# charliewatch-norf.net
KiCad netlist of a schematic drawn in EAGLE
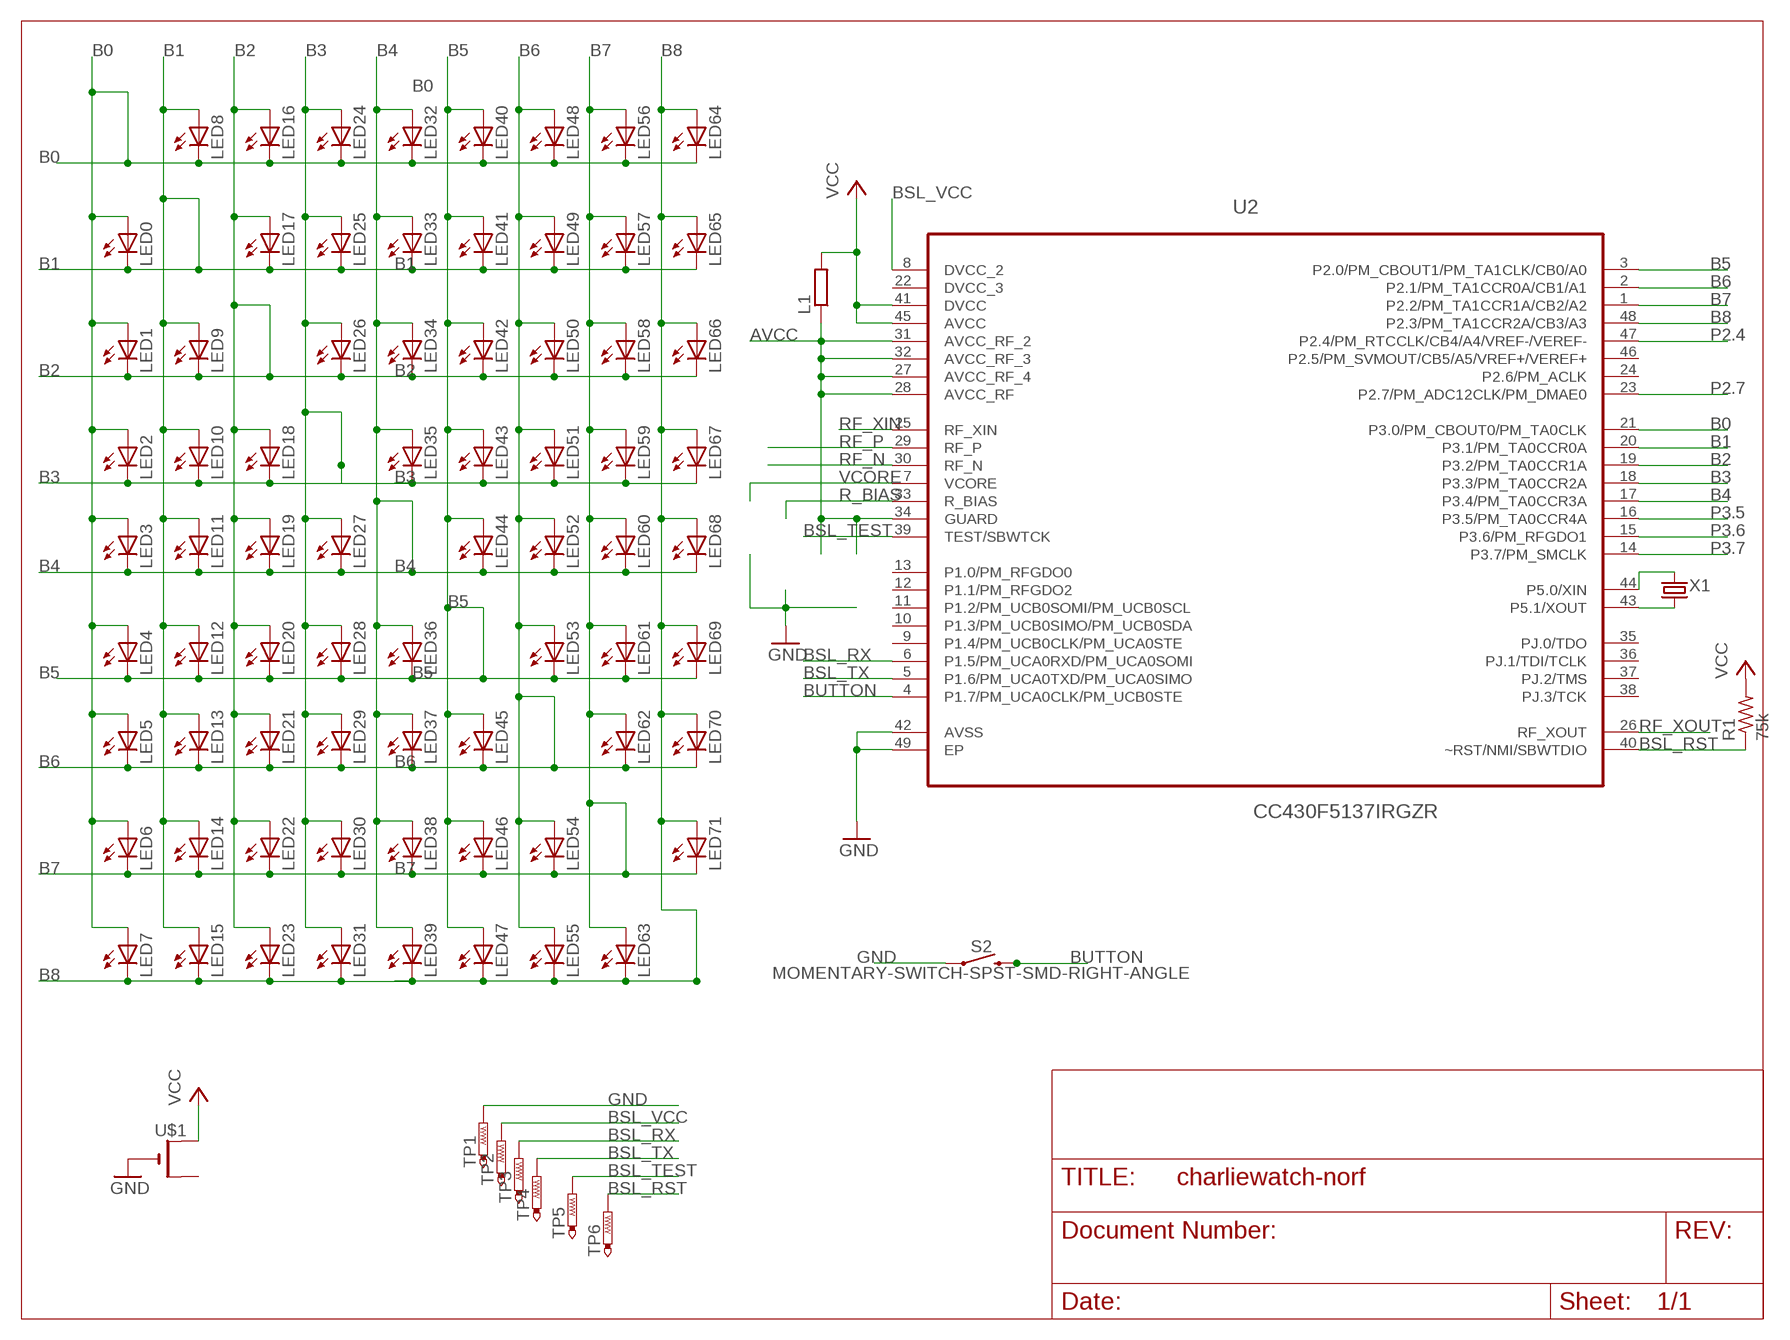
[diagram p0: schematic, sheet 1]

(export (version "E")
  (design (tool "Eeschema 10.0.6"))
  (components
    (comp (ref "L1")
      (value "R-EU_R0603")
      (footprint "eagle-import:R0603")
      (libsource (lib "eagle-import") (part "R-EU_R0603"))
    )
    (comp (ref "LED0")
      (value "LEDCHIPLED_0603")
      (footprint "eagle-import:CHIPLED_0603")
      (libsource (lib "eagle-import") (part "LEDCHIPLED_0603"))
    )
    (comp (ref "LED1")
      (value "LEDCHIPLED_0603")
      (footprint "eagle-import:CHIPLED_0603")
      (libsource (lib "eagle-import") (part "LEDCHIPLED_0603"))
    )
    (comp (ref "LED2")
      (value "LEDCHIPLED_0603")
      (footprint "eagle-import:CHIPLED_0603")
      (libsource (lib "eagle-import") (part "LEDCHIPLED_0603"))
    )
    (comp (ref "LED3")
      (value "LEDCHIPLED_0603")
      (footprint "eagle-import:CHIPLED_0603")
      (libsource (lib "eagle-import") (part "LEDCHIPLED_0603"))
    )
    (comp (ref "LED4")
      (value "LEDCHIPLED_0603")
      (footprint "eagle-import:CHIPLED_0603")
      (libsource (lib "eagle-import") (part "LEDCHIPLED_0603"))
    )
    (comp (ref "LED5")
      (value "LEDCHIPLED_0603")
      (footprint "eagle-import:CHIPLED_0603")
      (libsource (lib "eagle-import") (part "LEDCHIPLED_0603"))
    )
    (comp (ref "LED6")
      (value "LEDCHIPLED_0603")
      (footprint "eagle-import:CHIPLED_0603")
      (libsource (lib "eagle-import") (part "LEDCHIPLED_0603"))
    )
    (comp (ref "LED7")
      (value "LEDCHIPLED_0603")
      (footprint "eagle-import:CHIPLED_0603")
      (libsource (lib "eagle-import") (part "LEDCHIPLED_0603"))
    )
    (comp (ref "LED8")
      (value "LEDCHIPLED_0603")
      (footprint "eagle-import:CHIPLED_0603")
      (libsource (lib "eagle-import") (part "LEDCHIPLED_0603"))
    )
    (comp (ref "LED9")
      (value "LEDCHIPLED_0603")
      (footprint "eagle-import:CHIPLED_0603")
      (libsource (lib "eagle-import") (part "LEDCHIPLED_0603"))
    )
    (comp (ref "LED10")
      (value "LEDCHIPLED_0603")
      (footprint "eagle-import:CHIPLED_0603")
      (libsource (lib "eagle-import") (part "LEDCHIPLED_0603"))
    )
    (comp (ref "LED11")
      (value "LEDCHIPLED_0603")
      (footprint "eagle-import:CHIPLED_0603")
      (libsource (lib "eagle-import") (part "LEDCHIPLED_0603"))
    )
    (comp (ref "LED12")
      (value "LEDCHIPLED_0603")
      (footprint "eagle-import:CHIPLED_0603")
      (libsource (lib "eagle-import") (part "LEDCHIPLED_0603"))
    )
    (comp (ref "LED13")
      (value "LEDCHIPLED_0603")
      (footprint "eagle-import:CHIPLED_0603")
      (libsource (lib "eagle-import") (part "LEDCHIPLED_0603"))
    )
    (comp (ref "LED14")
      (value "LEDCHIPLED_0603")
      (footprint "eagle-import:CHIPLED_0603")
      (libsource (lib "eagle-import") (part "LEDCHIPLED_0603"))
    )
    (comp (ref "LED15")
      (value "LEDCHIPLED_0603")
      (footprint "eagle-import:CHIPLED_0603")
      (libsource (lib "eagle-import") (part "LEDCHIPLED_0603"))
    )
    (comp (ref "LED16")
      (value "LEDCHIPLED_0603")
      (footprint "eagle-import:CHIPLED_0603")
      (libsource (lib "eagle-import") (part "LEDCHIPLED_0603"))
    )
    (comp (ref "LED17")
      (value "LEDCHIPLED_0603")
      (footprint "eagle-import:CHIPLED_0603")
      (libsource (lib "eagle-import") (part "LEDCHIPLED_0603"))
    )
    (comp (ref "LED18")
      (value "LEDCHIPLED_0603")
      (footprint "eagle-import:CHIPLED_0603")
      (libsource (lib "eagle-import") (part "LEDCHIPLED_0603"))
    )
    (comp (ref "LED19")
      (value "LEDCHIPLED_0603")
      (footprint "eagle-import:CHIPLED_0603")
      (libsource (lib "eagle-import") (part "LEDCHIPLED_0603"))
    )
    (comp (ref "LED20")
      (value "LEDCHIPLED_0603")
      (footprint "eagle-import:CHIPLED_0603")
      (libsource (lib "eagle-import") (part "LEDCHIPLED_0603"))
    )
    (comp (ref "LED21")
      (value "LEDCHIPLED_0603")
      (footprint "eagle-import:CHIPLED_0603")
      (libsource (lib "eagle-import") (part "LEDCHIPLED_0603"))
    )
    (comp (ref "LED22")
      (value "LEDCHIPLED_0603")
      (footprint "eagle-import:CHIPLED_0603")
      (libsource (lib "eagle-import") (part "LEDCHIPLED_0603"))
    )
    (comp (ref "LED23")
      (value "LEDCHIPLED_0603")
      (footprint "eagle-import:CHIPLED_0603")
      (libsource (lib "eagle-import") (part "LEDCHIPLED_0603"))
    )
    (comp (ref "LED24")
      (value "LEDCHIPLED_0603")
      (footprint "eagle-import:CHIPLED_0603")
      (libsource (lib "eagle-import") (part "LEDCHIPLED_0603"))
    )
    (comp (ref "LED25")
      (value "LEDCHIPLED_0603")
      (footprint "eagle-import:CHIPLED_0603")
      (libsource (lib "eagle-import") (part "LEDCHIPLED_0603"))
    )
    (comp (ref "LED26")
      (value "LEDCHIPLED_0603")
      (footprint "eagle-import:CHIPLED_0603")
      (libsource (lib "eagle-import") (part "LEDCHIPLED_0603"))
    )
    (comp (ref "LED27")
      (value "LEDCHIPLED_0603")
      (footprint "eagle-import:CHIPLED_0603")
      (libsource (lib "eagle-import") (part "LEDCHIPLED_0603"))
    )
    (comp (ref "LED28")
      (value "LEDCHIPLED_0603")
      (footprint "eagle-import:CHIPLED_0603")
      (libsource (lib "eagle-import") (part "LEDCHIPLED_0603"))
    )
    (comp (ref "LED29")
      (value "LEDCHIPLED_0603")
      (footprint "eagle-import:CHIPLED_0603")
      (libsource (lib "eagle-import") (part "LEDCHIPLED_0603"))
    )
    (comp (ref "LED30")
      (value "LEDCHIPLED_0603")
      (footprint "eagle-import:CHIPLED_0603")
      (libsource (lib "eagle-import") (part "LEDCHIPLED_0603"))
    )
    (comp (ref "LED31")
      (value "LEDCHIPLED_0603")
      (footprint "eagle-import:CHIPLED_0603")
      (libsource (lib "eagle-import") (part "LEDCHIPLED_0603"))
    )
    (comp (ref "LED32")
      (value "LEDCHIPLED_0603")
      (footprint "eagle-import:CHIPLED_0603")
      (libsource (lib "eagle-import") (part "LEDCHIPLED_0603"))
    )
    (comp (ref "LED33")
      (value "LEDCHIPLED_0603")
      (footprint "eagle-import:CHIPLED_0603")
      (libsource (lib "eagle-import") (part "LEDCHIPLED_0603"))
    )
    (comp (ref "LED34")
      (value "LEDCHIPLED_0603")
      (footprint "eagle-import:CHIPLED_0603")
      (libsource (lib "eagle-import") (part "LEDCHIPLED_0603"))
    )
    (comp (ref "LED35")
      (value "LEDCHIPLED_0603")
      (footprint "eagle-import:CHIPLED_0603")
      (libsource (lib "eagle-import") (part "LEDCHIPLED_0603"))
    )
    (comp (ref "LED36")
      (value "LEDCHIPLED_0603")
      (footprint "eagle-import:CHIPLED_0603")
      (libsource (lib "eagle-import") (part "LEDCHIPLED_0603"))
    )
    (comp (ref "LED37")
      (value "LEDCHIPLED_0603")
      (footprint "eagle-import:CHIPLED_0603")
      (libsource (lib "eagle-import") (part "LEDCHIPLED_0603"))
    )
    (comp (ref "LED38")
      (value "LEDCHIPLED_0603")
      (footprint "eagle-import:CHIPLED_0603")
      (libsource (lib "eagle-import") (part "LEDCHIPLED_0603"))
    )
    (comp (ref "LED39")
      (value "LEDCHIPLED_0603")
      (footprint "eagle-import:CHIPLED_0603")
      (libsource (lib "eagle-import") (part "LEDCHIPLED_0603"))
    )
    (comp (ref "LED40")
      (value "LEDCHIPLED_0603")
      (footprint "eagle-import:CHIPLED_0603")
      (libsource (lib "eagle-import") (part "LEDCHIPLED_0603"))
    )
    (comp (ref "LED41")
      (value "LEDCHIPLED_0603")
      (footprint "eagle-import:CHIPLED_0603")
      (libsource (lib "eagle-import") (part "LEDCHIPLED_0603"))
    )
    (comp (ref "LED42")
      (value "LEDCHIPLED_0603")
      (footprint "eagle-import:CHIPLED_0603")
      (libsource (lib "eagle-import") (part "LEDCHIPLED_0603"))
    )
    (comp (ref "LED43")
      (value "LEDCHIPLED_0603")
      (footprint "eagle-import:CHIPLED_0603")
      (libsource (lib "eagle-import") (part "LEDCHIPLED_0603"))
    )
    (comp (ref "LED44")
      (value "LEDCHIPLED_0603")
      (footprint "eagle-import:CHIPLED_0603")
      (libsource (lib "eagle-import") (part "LEDCHIPLED_0603"))
    )
    (comp (ref "LED45")
      (value "LEDCHIPLED_0603")
      (footprint "eagle-import:CHIPLED_0603")
      (libsource (lib "eagle-import") (part "LEDCHIPLED_0603"))
    )
    (comp (ref "LED46")
      (value "LEDCHIPLED_0603")
      (footprint "eagle-import:CHIPLED_0603")
      (libsource (lib "eagle-import") (part "LEDCHIPLED_0603"))
    )
    (comp (ref "LED47")
      (value "LEDCHIPLED_0603")
      (footprint "eagle-import:CHIPLED_0603")
      (libsource (lib "eagle-import") (part "LEDCHIPLED_0603"))
    )
    (comp (ref "LED48")
      (value "LEDCHIPLED_0603")
      (footprint "eagle-import:CHIPLED_0603")
      (libsource (lib "eagle-import") (part "LEDCHIPLED_0603"))
    )
    (comp (ref "LED49")
      (value "LEDCHIPLED_0603")
      (footprint "eagle-import:CHIPLED_0603")
      (libsource (lib "eagle-import") (part "LEDCHIPLED_0603"))
    )
    (comp (ref "LED50")
      (value "LEDCHIPLED_0603")
      (footprint "eagle-import:CHIPLED_0603")
      (libsource (lib "eagle-import") (part "LEDCHIPLED_0603"))
    )
    (comp (ref "LED51")
      (value "LEDCHIPLED_0603")
      (footprint "eagle-import:CHIPLED_0603")
      (libsource (lib "eagle-import") (part "LEDCHIPLED_0603"))
    )
    (comp (ref "LED52")
      (value "LEDCHIPLED_0603")
      (footprint "eagle-import:CHIPLED_0603")
      (libsource (lib "eagle-import") (part "LEDCHIPLED_0603"))
    )
    (comp (ref "LED53")
      (value "LEDCHIPLED_0603")
      (footprint "eagle-import:CHIPLED_0603")
      (libsource (lib "eagle-import") (part "LEDCHIPLED_0603"))
    )
    (comp (ref "LED54")
      (value "LEDCHIPLED_0603")
      (footprint "eagle-import:CHIPLED_0603")
      (libsource (lib "eagle-import") (part "LEDCHIPLED_0603"))
    )
    (comp (ref "LED55")
      (value "LEDCHIPLED_0603")
      (footprint "eagle-import:CHIPLED_0603")
      (libsource (lib "eagle-import") (part "LEDCHIPLED_0603"))
    )
    (comp (ref "LED56")
      (value "LEDCHIPLED_0603")
      (footprint "eagle-import:CHIPLED_0603")
      (libsource (lib "eagle-import") (part "LEDCHIPLED_0603"))
    )
    (comp (ref "LED57")
      (value "LEDCHIPLED_0603")
      (footprint "eagle-import:CHIPLED_0603")
      (libsource (lib "eagle-import") (part "LEDCHIPLED_0603"))
    )
    (comp (ref "LED58")
      (value "LEDCHIPLED_0603")
      (footprint "eagle-import:CHIPLED_0603")
      (libsource (lib "eagle-import") (part "LEDCHIPLED_0603"))
    )
    (comp (ref "LED59")
      (value "LEDCHIPLED_0603")
      (footprint "eagle-import:CHIPLED_0603")
      (libsource (lib "eagle-import") (part "LEDCHIPLED_0603"))
    )
    (comp (ref "LED60")
      (value "LEDCHIPLED_0603")
      (footprint "eagle-import:CHIPLED_0603")
      (libsource (lib "eagle-import") (part "LEDCHIPLED_0603"))
    )
    (comp (ref "LED61")
      (value "LEDCHIPLED_0603")
      (footprint "eagle-import:CHIPLED_0603")
      (libsource (lib "eagle-import") (part "LEDCHIPLED_0603"))
    )
    (comp (ref "LED62")
      (value "LEDCHIPLED_0603")
      (footprint "eagle-import:CHIPLED_0603")
      (libsource (lib "eagle-import") (part "LEDCHIPLED_0603"))
    )
    (comp (ref "LED63")
      (value "LEDCHIPLED_0603")
      (footprint "eagle-import:CHIPLED_0603")
      (libsource (lib "eagle-import") (part "LEDCHIPLED_0603"))
    )
    (comp (ref "LED64")
      (value "LEDCHIPLED_0603")
      (footprint "eagle-import:CHIPLED_0603")
      (libsource (lib "eagle-import") (part "LEDCHIPLED_0603"))
    )
    (comp (ref "LED65")
      (value "LEDCHIPLED_0603")
      (footprint "eagle-import:CHIPLED_0603")
      (libsource (lib "eagle-import") (part "LEDCHIPLED_0603"))
    )
    (comp (ref "LED66")
      (value "LEDCHIPLED_0603")
      (footprint "eagle-import:CHIPLED_0603")
      (libsource (lib "eagle-import") (part "LEDCHIPLED_0603"))
    )
    (comp (ref "LED67")
      (value "LEDCHIPLED_0603")
      (footprint "eagle-import:CHIPLED_0603")
      (libsource (lib "eagle-import") (part "LEDCHIPLED_0603"))
    )
    (comp (ref "LED68")
      (value "LEDCHIPLED_0603")
      (footprint "eagle-import:CHIPLED_0603")
      (libsource (lib "eagle-import") (part "LEDCHIPLED_0603"))
    )
    (comp (ref "LED69")
      (value "LEDCHIPLED_0603")
      (footprint "eagle-import:CHIPLED_0603")
      (libsource (lib "eagle-import") (part "LEDCHIPLED_0603"))
    )
    (comp (ref "LED70")
      (value "LEDCHIPLED_0603")
      (footprint "eagle-import:CHIPLED_0603")
      (libsource (lib "eagle-import") (part "LEDCHIPLED_0603"))
    )
    (comp (ref "LED71")
      (value "LEDCHIPLED_0603")
      (footprint "eagle-import:CHIPLED_0603")
      (libsource (lib "eagle-import") (part "LEDCHIPLED_0603"))
    )
    (comp (ref "R1")
      (value "75k")
      (footprint "eagle-import:R0402")
      (libsource (lib "eagle-import") (part "R-US_R0402"))
    )
    (comp (ref "S2")
      (value "MOMENTARY-SWITCH-SPST-SMD-RIGHT-ANGLE")
      (footprint "eagle-import:TACTILE_SWITCH_SMD_RIGHT_ANGLE")
      (libsource (lib "eagle-import") (part "MOMENTARY-SWITCH-SPST-SMD-RIGHT-ANGLE"))
    )
    (comp (ref "TP1")
      (value "PTR1TP10SQ")
      (footprint "eagle-import:TP10SQ")
      (libsource (lib "eagle-import") (part "PTR1TP10SQ"))
    )
    (comp (ref "TP2")
      (value "PTR1TP10R")
      (footprint "eagle-import:TP10R")
      (libsource (lib "eagle-import") (part "PTR1TP10R"))
    )
    (comp (ref "TP3")
      (value "PTR1TP10R")
      (footprint "eagle-import:TP10R")
      (libsource (lib "eagle-import") (part "PTR1TP10R"))
    )
    (comp (ref "TP4")
      (value "PTR1TP10R")
      (footprint "eagle-import:TP10R")
      (libsource (lib "eagle-import") (part "PTR1TP10R"))
    )
    (comp (ref "TP5")
      (value "PTR1TP10R")
      (footprint "eagle-import:TP10R")
      (libsource (lib "eagle-import") (part "PTR1TP10R"))
    )
    (comp (ref "TP6")
      (value "PTR1TP10R")
      (footprint "eagle-import:TP10R")
      (libsource (lib "eagle-import") (part "PTR1TP10R"))
    )
    (comp (ref "U$1")
      (value "CR2032SMT")
      (footprint "eagle-import:CR2032-SMD")
      (libsource (lib "eagle-import") (part "CR2032SMT"))
    )
    (comp (ref "U2")
      (value "CC430F5137IRGZR")
      (footprint "eagle-import:QFN50P700X700X100-49N")
      (libsource (lib "eagle-import") (part "CC430F5137IRGZR"))
    )
    (comp (ref "X1")
      (value "CRYSTALS-NOGND-IQXC-25")
      (footprint "eagle-import:2.0X1.2-2PAD")
      (libsource (lib "eagle-import") (part "CRYSTALS-NOGND-IQXC-25"))
    )
  )
  (nets
    (net (code "1") (name "/AVCC") (class "Default")
      (node (ref "L1") (pin "1") (pinfunction "1_1") (pintype "passive"))
      (node (ref "U2") (pin "27") (pinfunction "AVCC_RF_4_27") (pintype "power_in"))
      (node (ref "U2") (pin "28") (pinfunction "AVCC_RF_28") (pintype "power_in"))
      (node (ref "U2") (pin "31") (pinfunction "AVCC_RF_2_31") (pintype "power_in"))
      (node (ref "U2") (pin "32") (pinfunction "AVCC_RF_3_32") (pintype "power_in"))
      (node (ref "U2") (pin "34") (pinfunction "GUARD_34") (pintype "input"))
    )
    (net (code "2") (name "/B0") (class "Default")
      (node (ref "LED0") (pin "A") (pinfunction "A_A") (pintype "passive"))
      (node (ref "LED1") (pin "A") (pinfunction "A_A") (pintype "passive"))
      (node (ref "LED16") (pin "C") (pinfunction "C_C") (pintype "passive"))
      (node (ref "LED2") (pin "A") (pinfunction "A_A") (pintype "passive"))
      (node (ref "LED24") (pin "C") (pinfunction "C_C") (pintype "passive"))
      (node (ref "LED3") (pin "A") (pinfunction "A_A") (pintype "passive"))
      (node (ref "LED32") (pin "C") (pinfunction "C_C") (pintype "passive"))
      (node (ref "LED4") (pin "A") (pinfunction "A_A") (pintype "passive"))
      (node (ref "LED40") (pin "C") (pinfunction "C_C") (pintype "passive"))
      (node (ref "LED48") (pin "C") (pinfunction "C_C") (pintype "passive"))
      (node (ref "LED5") (pin "A") (pinfunction "A_A") (pintype "passive"))
      (node (ref "LED56") (pin "C") (pinfunction "C_C") (pintype "passive"))
      (node (ref "LED6") (pin "A") (pinfunction "A_A") (pintype "passive"))
      (node (ref "LED64") (pin "C") (pinfunction "C_C") (pintype "passive"))
      (node (ref "LED7") (pin "A") (pinfunction "A_A") (pintype "passive"))
      (node (ref "LED8") (pin "C") (pinfunction "C_C") (pintype "passive"))
      (node (ref "U2") (pin "21") (pinfunction "P3.0/PM_CBOUT0/PM_TA0CLK_21") (pintype "bidirectional"))
    )
    (net (code "3") (name "/B1") (class "Default")
      (node (ref "LED0") (pin "C") (pinfunction "C_C") (pintype "passive"))
      (node (ref "LED10") (pin "A") (pinfunction "A_A") (pintype "passive"))
      (node (ref "LED11") (pin "A") (pinfunction "A_A") (pintype "passive"))
      (node (ref "LED12") (pin "A") (pinfunction "A_A") (pintype "passive"))
      (node (ref "LED13") (pin "A") (pinfunction "A_A") (pintype "passive"))
      (node (ref "LED14") (pin "A") (pinfunction "A_A") (pintype "passive"))
      (node (ref "LED15") (pin "A") (pinfunction "A_A") (pintype "passive"))
      (node (ref "LED17") (pin "C") (pinfunction "C_C") (pintype "passive"))
      (node (ref "LED25") (pin "C") (pinfunction "C_C") (pintype "passive"))
      (node (ref "LED33") (pin "C") (pinfunction "C_C") (pintype "passive"))
      (node (ref "LED41") (pin "C") (pinfunction "C_C") (pintype "passive"))
      (node (ref "LED49") (pin "C") (pinfunction "C_C") (pintype "passive"))
      (node (ref "LED57") (pin "C") (pinfunction "C_C") (pintype "passive"))
      (node (ref "LED65") (pin "C") (pinfunction "C_C") (pintype "passive"))
      (node (ref "LED8") (pin "A") (pinfunction "A_A") (pintype "passive"))
      (node (ref "LED9") (pin "A") (pinfunction "A_A") (pintype "passive"))
      (node (ref "U2") (pin "20") (pinfunction "P3.1/PM_TA0CCR0A_20") (pintype "bidirectional"))
    )
    (net (code "4") (name "/B2") (class "Default")
      (node (ref "LED1") (pin "C") (pinfunction "C_C") (pintype "passive"))
      (node (ref "LED16") (pin "A") (pinfunction "A_A") (pintype "passive"))
      (node (ref "LED17") (pin "A") (pinfunction "A_A") (pintype "passive"))
      (node (ref "LED18") (pin "A") (pinfunction "A_A") (pintype "passive"))
      (node (ref "LED19") (pin "A") (pinfunction "A_A") (pintype "passive"))
      (node (ref "LED20") (pin "A") (pinfunction "A_A") (pintype "passive"))
      (node (ref "LED21") (pin "A") (pinfunction "A_A") (pintype "passive"))
      (node (ref "LED22") (pin "A") (pinfunction "A_A") (pintype "passive"))
      (node (ref "LED23") (pin "A") (pinfunction "A_A") (pintype "passive"))
      (node (ref "LED26") (pin "C") (pinfunction "C_C") (pintype "passive"))
      (node (ref "LED34") (pin "C") (pinfunction "C_C") (pintype "passive"))
      (node (ref "LED42") (pin "C") (pinfunction "C_C") (pintype "passive"))
      (node (ref "LED50") (pin "C") (pinfunction "C_C") (pintype "passive"))
      (node (ref "LED58") (pin "C") (pinfunction "C_C") (pintype "passive"))
      (node (ref "LED66") (pin "C") (pinfunction "C_C") (pintype "passive"))
      (node (ref "LED9") (pin "C") (pinfunction "C_C") (pintype "passive"))
      (node (ref "U2") (pin "19") (pinfunction "P3.2/PM_TA0CCR1A_19") (pintype "bidirectional"))
    )
    (net (code "5") (name "/B3") (class "Default")
      (node (ref "LED10") (pin "C") (pinfunction "C_C") (pintype "passive"))
      (node (ref "LED18") (pin "C") (pinfunction "C_C") (pintype "passive"))
      (node (ref "LED2") (pin "C") (pinfunction "C_C") (pintype "passive"))
      (node (ref "LED24") (pin "A") (pinfunction "A_A") (pintype "passive"))
      (node (ref "LED25") (pin "A") (pinfunction "A_A") (pintype "passive"))
      (node (ref "LED26") (pin "A") (pinfunction "A_A") (pintype "passive"))
      (node (ref "LED27") (pin "A") (pinfunction "A_A") (pintype "passive"))
      (node (ref "LED28") (pin "A") (pinfunction "A_A") (pintype "passive"))
      (node (ref "LED29") (pin "A") (pinfunction "A_A") (pintype "passive"))
      (node (ref "LED30") (pin "A") (pinfunction "A_A") (pintype "passive"))
      (node (ref "LED31") (pin "A") (pinfunction "A_A") (pintype "passive"))
      (node (ref "LED35") (pin "C") (pinfunction "C_C") (pintype "passive"))
      (node (ref "LED43") (pin "C") (pinfunction "C_C") (pintype "passive"))
      (node (ref "LED51") (pin "C") (pinfunction "C_C") (pintype "passive"))
      (node (ref "LED59") (pin "C") (pinfunction "C_C") (pintype "passive"))
      (node (ref "LED67") (pin "C") (pinfunction "C_C") (pintype "passive"))
      (node (ref "U2") (pin "18") (pinfunction "P3.3/PM_TA0CCR2A_18") (pintype "bidirectional"))
    )
    (net (code "6") (name "/B4") (class "Default")
      (node (ref "LED11") (pin "C") (pinfunction "C_C") (pintype "passive"))
      (node (ref "LED19") (pin "C") (pinfunction "C_C") (pintype "passive"))
      (node (ref "LED27") (pin "C") (pinfunction "C_C") (pintype "passive"))
      (node (ref "LED3") (pin "C") (pinfunction "C_C") (pintype "passive"))
      (node (ref "LED32") (pin "A") (pinfunction "A_A") (pintype "passive"))
      (node (ref "LED33") (pin "A") (pinfunction "A_A") (pintype "passive"))
      (node (ref "LED34") (pin "A") (pinfunction "A_A") (pintype "passive"))
      (node (ref "LED35") (pin "A") (pinfunction "A_A") (pintype "passive"))
      (node (ref "LED36") (pin "A") (pinfunction "A_A") (pintype "passive"))
      (node (ref "LED37") (pin "A") (pinfunction "A_A") (pintype "passive"))
      (node (ref "LED38") (pin "A") (pinfunction "A_A") (pintype "passive"))
      (node (ref "LED39") (pin "A") (pinfunction "A_A") (pintype "passive"))
      (node (ref "LED44") (pin "C") (pinfunction "C_C") (pintype "passive"))
      (node (ref "LED52") (pin "C") (pinfunction "C_C") (pintype "passive"))
      (node (ref "LED60") (pin "C") (pinfunction "C_C") (pintype "passive"))
      (node (ref "LED68") (pin "C") (pinfunction "C_C") (pintype "passive"))
      (node (ref "U2") (pin "17") (pinfunction "P3.4/PM_TA0CCR3A_17") (pintype "bidirectional"))
    )
    (net (code "7") (name "/B5") (class "Default")
      (node (ref "LED12") (pin "C") (pinfunction "C_C") (pintype "passive"))
      (node (ref "LED20") (pin "C") (pinfunction "C_C") (pintype "passive"))
      (node (ref "LED28") (pin "C") (pinfunction "C_C") (pintype "passive"))
      (node (ref "LED36") (pin "C") (pinfunction "C_C") (pintype "passive"))
      (node (ref "LED4") (pin "C") (pinfunction "C_C") (pintype "passive"))
      (node (ref "LED40") (pin "A") (pinfunction "A_A") (pintype "passive"))
      (node (ref "LED41") (pin "A") (pinfunction "A_A") (pintype "passive"))
      (node (ref "LED42") (pin "A") (pinfunction "A_A") (pintype "passive"))
      (node (ref "LED43") (pin "A") (pinfunction "A_A") (pintype "passive"))
      (node (ref "LED44") (pin "A") (pinfunction "A_A") (pintype "passive"))
      (node (ref "LED45") (pin "A") (pinfunction "A_A") (pintype "passive"))
      (node (ref "LED46") (pin "A") (pinfunction "A_A") (pintype "passive"))
      (node (ref "LED47") (pin "A") (pinfunction "A_A") (pintype "passive"))
      (node (ref "LED53") (pin "C") (pinfunction "C_C") (pintype "passive"))
      (node (ref "LED61") (pin "C") (pinfunction "C_C") (pintype "passive"))
      (node (ref "LED69") (pin "C") (pinfunction "C_C") (pintype "passive"))
      (node (ref "U2") (pin "3") (pinfunction "P2.0/PM_CBOUT1/PM_TA1CLK/CB0/A0_3") (pintype "bidirectional"))
    )
    (net (code "8") (name "/B6") (class "Default")
      (node (ref "LED13") (pin "C") (pinfunction "C_C") (pintype "passive"))
      (node (ref "LED21") (pin "C") (pinfunction "C_C") (pintype "passive"))
      (node (ref "LED29") (pin "C") (pinfunction "C_C") (pintype "passive"))
      (node (ref "LED37") (pin "C") (pinfunction "C_C") (pintype "passive"))
      (node (ref "LED45") (pin "C") (pinfunction "C_C") (pintype "passive"))
      (node (ref "LED48") (pin "A") (pinfunction "A_A") (pintype "passive"))
      (node (ref "LED49") (pin "A") (pinfunction "A_A") (pintype "passive"))
      (node (ref "LED5") (pin "C") (pinfunction "C_C") (pintype "passive"))
      (node (ref "LED50") (pin "A") (pinfunction "A_A") (pintype "passive"))
      (node (ref "LED51") (pin "A") (pinfunction "A_A") (pintype "passive"))
      (node (ref "LED52") (pin "A") (pinfunction "A_A") (pintype "passive"))
      (node (ref "LED53") (pin "A") (pinfunction "A_A") (pintype "passive"))
      (node (ref "LED54") (pin "A") (pinfunction "A_A") (pintype "passive"))
      (node (ref "LED55") (pin "A") (pinfunction "A_A") (pintype "passive"))
      (node (ref "LED62") (pin "C") (pinfunction "C_C") (pintype "passive"))
      (node (ref "LED70") (pin "C") (pinfunction "C_C") (pintype "passive"))
      (node (ref "U2") (pin "2") (pinfunction "P2.1/PM_TA1CCR0A/CB1/A1_2") (pintype "bidirectional"))
    )
    (net (code "9") (name "/B7") (class "Default")
      (node (ref "LED14") (pin "C") (pinfunction "C_C") (pintype "passive"))
      (node (ref "LED22") (pin "C") (pinfunction "C_C") (pintype "passive"))
      (node (ref "LED30") (pin "C") (pinfunction "C_C") (pintype "passive"))
      (node (ref "LED38") (pin "C") (pinfunction "C_C") (pintype "passive"))
      (node (ref "LED46") (pin "C") (pinfunction "C_C") (pintype "passive"))
      (node (ref "LED54") (pin "C") (pinfunction "C_C") (pintype "passive"))
      (node (ref "LED56") (pin "A") (pinfunction "A_A") (pintype "passive"))
      (node (ref "LED57") (pin "A") (pinfunction "A_A") (pintype "passive"))
      (node (ref "LED58") (pin "A") (pinfunction "A_A") (pintype "passive"))
      (node (ref "LED59") (pin "A") (pinfunction "A_A") (pintype "passive"))
      (node (ref "LED6") (pin "C") (pinfunction "C_C") (pintype "passive"))
      (node (ref "LED60") (pin "A") (pinfunction "A_A") (pintype "passive"))
      (node (ref "LED61") (pin "A") (pinfunction "A_A") (pintype "passive"))
      (node (ref "LED62") (pin "A") (pinfunction "A_A") (pintype "passive"))
      (node (ref "LED63") (pin "A") (pinfunction "A_A") (pintype "passive"))
      (node (ref "LED71") (pin "C") (pinfunction "C_C") (pintype "passive"))
      (node (ref "U2") (pin "1") (pinfunction "P2.2/PM_TA1CCR1A/CB2/A2_1") (pintype "bidirectional"))
    )
    (net (code "10") (name "/B8") (class "Default")
      (node (ref "LED15") (pin "C") (pinfunction "C_C") (pintype "passive"))
      (node (ref "LED23") (pin "C") (pinfunction "C_C") (pintype "passive"))
      (node (ref "LED31") (pin "C") (pinfunction "C_C") (pintype "passive"))
      (node (ref "LED39") (pin "C") (pinfunction "C_C") (pintype "passive"))
      (node (ref "LED47") (pin "C") (pinfunction "C_C") (pintype "passive"))
      (node (ref "LED55") (pin "C") (pinfunction "C_C") (pintype "passive"))
      (node (ref "LED63") (pin "C") (pinfunction "C_C") (pintype "passive"))
      (node (ref "LED64") (pin "A") (pinfunction "A_A") (pintype "passive"))
      (node (ref "LED65") (pin "A") (pinfunction "A_A") (pintype "passive"))
      (node (ref "LED66") (pin "A") (pinfunction "A_A") (pintype "passive"))
      (node (ref "LED67") (pin "A") (pinfunction "A_A") (pintype "passive"))
      (node (ref "LED68") (pin "A") (pinfunction "A_A") (pintype "passive"))
      (node (ref "LED69") (pin "A") (pinfunction "A_A") (pintype "passive"))
      (node (ref "LED7") (pin "C") (pinfunction "C_C") (pintype "passive"))
      (node (ref "LED70") (pin "A") (pinfunction "A_A") (pintype "passive"))
      (node (ref "LED71") (pin "A") (pinfunction "A_A") (pintype "passive"))
      (node (ref "U2") (pin "48") (pinfunction "P2.3/PM_TA1CCR2A/CB3/A3_48") (pintype "bidirectional"))
    )
    (net (code "11") (name "/BSL_RST") (class "Default")
      (node (ref "R1") (pin "1") (pinfunction "1_1") (pintype "passive"))
      (node (ref "TP6") (pin "TP") (pinfunction "TP_TP") (pintype "input"))
      (node (ref "U2") (pin "40") (pinfunction "~{RST/NMI/SBWTDIO}_40") (pintype "bidirectional"))
    )
    (net (code "12") (name "/BSL_RX") (class "Default")
      (node (ref "TP3") (pin "TP") (pinfunction "TP_TP") (pintype "input"))
      (node (ref "U2") (pin "6") (pinfunction "P1.5/PM_UCA0RXD/PM_UCA0SOMI_6") (pintype "bidirectional"))
    )
    (net (code "13") (name "/BSL_TEST") (class "Default")
      (node (ref "TP5") (pin "TP") (pinfunction "TP_TP") (pintype "input"))
      (node (ref "U2") (pin "39") (pinfunction "TEST/SBWTCK_39") (pintype "input"))
    )
    (net (code "14") (name "/BSL_TX") (class "Default")
      (node (ref "TP4") (pin "TP") (pinfunction "TP_TP") (pintype "input"))
      (node (ref "U2") (pin "5") (pinfunction "P1.6/PM_UCA0TXD/PM_UCA0SIMO_5") (pintype "bidirectional"))
    )
    (net (code "15") (name "/BSL_VCC") (class "Default")
      (node (ref "TP2") (pin "TP") (pinfunction "TP_TP") (pintype "input"))
      (node (ref "U2") (pin "8") (pinfunction "DVCC_2_8") (pintype "power_in"))
    )
    (net (code "16") (name "/BUTTON") (class "Default")
      (node (ref "S2") (pin "2") (pinfunction "2_2") (pintype "passive"))
      (node (ref "U2") (pin "4") (pinfunction "P1.7/PM_UCA0CLK/PM_UCB0STE_4") (pintype "bidirectional"))
    )
    (net (code "17") (name "/DVCC_3") (class "Default")
      (node (ref "U2") (pin "22") (pinfunction "DVCC_3_22") (pintype "power_in"))
    )
    (net (code "18") (name "/P2.4") (class "Default")
      (node (ref "U2") (pin "47") (pinfunction "P2.4/PM_RTCCLK/CB4/A4/VREF-/VEREF-_47") (pintype "bidirectional"))
    )
    (net (code "19") (name "/P2.7") (class "Default")
      (node (ref "U2") (pin "23") (pinfunction "P2.7/PM_ADC12CLK/PM_DMAE0_23") (pintype "bidirectional"))
    )
    (net (code "20") (name "/P3.5") (class "Default")
      (node (ref "U2") (pin "16") (pinfunction "P3.5/PM_TA0CCR4A_16") (pintype "bidirectional"))
    )
    (net (code "21") (name "/P3.6") (class "Default")
      (node (ref "U2") (pin "15") (pinfunction "P3.6/PM_RFGDO1_15") (pintype "bidirectional"))
    )
    (net (code "22") (name "/P3.7") (class "Default")
      (node (ref "U2") (pin "14") (pinfunction "P3.7/PM_SMCLK_14") (pintype "bidirectional"))
    )
    (net (code "23") (name "/RF_N") (class "Default")
      (node (ref "U2") (pin "30") (pinfunction "RF_N_30") (pintype "bidirectional"))
    )
    (net (code "24") (name "/RF_P") (class "Default")
      (node (ref "U2") (pin "29") (pinfunction "RF_P_29") (pintype "bidirectional"))
    )
    (net (code "25") (name "/RF_XIN") (class "Default")
      (node (ref "U2") (pin "25") (pinfunction "RF_XIN_25") (pintype "input"))
    )
    (net (code "26") (name "/RF_XOUT") (class "Default")
      (node (ref "U2") (pin "26") (pinfunction "RF_XOUT_26") (pintype "output"))
    )
    (net (code "27") (name "/R_BIAS") (class "Default")
      (node (ref "U2") (pin "33") (pinfunction "R_BIAS_33") (pintype "input"))
    )
    (net (code "28") (name "/VCORE") (class "Default")
      (node (ref "U2") (pin "7") (pinfunction "VCORE_7") (pintype "input"))
    )
    (net (code "29") (name "GND") (class "Default")
      (node (ref "S2") (pin "1") (pinfunction "1_1") (pintype "passive"))
      (node (ref "TP1") (pin "TP") (pinfunction "TP_TP") (pintype "input"))
      (node (ref "U$1") (pin "-") (pinfunction "-_-") (pintype "passive"))
      (node (ref "U2") (pin "42") (pinfunction "AVSS_42") (pintype "passive"))
      (node (ref "U2") (pin "49") (pinfunction "EP_49") (pintype "passive"))
    )
    (net (code "30") (name "Net-(U2-P5.0{slash}XIN)") (class "Default")
      (node (ref "U2") (pin "44") (pinfunction "P5.0/XIN_44") (pintype "bidirectional"))
      (node (ref "X1") (pin "2") (pinfunction "2_2") (pintype "passive"))
    )
    (net (code "31") (name "Net-(U2-P5.1{slash}XOUT)") (class "Default")
      (node (ref "U2") (pin "43") (pinfunction "P5.1/XOUT_43") (pintype "bidirectional"))
      (node (ref "X1") (pin "1") (pinfunction "1_1") (pintype "passive"))
    )
    (net (code "32") (name "VCC") (class "Default")
      (node (ref "L1") (pin "2") (pinfunction "2_2") (pintype "passive"))
      (node (ref "R1") (pin "2") (pinfunction "2_2") (pintype "passive"))
      (node (ref "U$1") (pin "+$1") (pinfunction "+_+$1") (pintype "passive"))
      (node (ref "U2") (pin "41") (pinfunction "DVCC_41") (pintype "power_in"))
      (node (ref "U2") (pin "45") (pinfunction "AVCC_45") (pintype "power_in"))
    )
    (net (code "33") (name "unconnected-(U$1-+1-Pad+$2)") (class "Default")
      (node (ref "U$1") (pin "+$2") (pinfunction "+1_+$2") (pintype "passive"))
    )
    (net (code "34") (name "unconnected-(U2-P1.0{slash}PM_RFGDO0-Pad13)") (class "Default")
      (node (ref "U2") (pin "13") (pinfunction "P1.0/PM_RFGDO0_13") (pintype "bidirectional"))
    )
    (net (code "35") (name "unconnected-(U2-P1.1{slash}PM_RFGDO2-Pad12)") (class "Default")
      (node (ref "U2") (pin "12") (pinfunction "P1.1/PM_RFGDO2_12") (pintype "bidirectional"))
    )
    (net (code "36") (name "unconnected-(U2-P1.2{slash}PM_UCB0SOMI{slash}PM_UCB0SCL-Pad11)") (class "Default")
      (node (ref "U2") (pin "11") (pinfunction "P1.2/PM_UCB0SOMI/PM_UCB0SCL_11") (pintype "bidirectional"))
    )
    (net (code "37") (name "unconnected-(U2-P1.3{slash}PM_UCB0SIMO{slash}PM_UCB0SDA-Pad10)") (class "Default")
      (node (ref "U2") (pin "10") (pinfunction "P1.3/PM_UCB0SIMO/PM_UCB0SDA_10") (pintype "bidirectional"))
    )
    (net (code "38") (name "unconnected-(U2-P1.4{slash}PM_UCB0CLK{slash}PM_UCA0STE-Pad9)") (class "Default")
      (node (ref "U2") (pin "9") (pinfunction "P1.4/PM_UCB0CLK/PM_UCA0STE_9") (pintype "bidirectional"))
    )
    (net (code "39") (name "unconnected-(U2-P2.5{slash}PM_SVMOUT{slash}CB5{slash}A5{slash}VREF+{slash}VEREF+-Pad46)") (class "Default")
      (node (ref "U2") (pin "46") (pinfunction "P2.5/PM_SVMOUT/CB5/A5/VREF+/VEREF+_46") (pintype "bidirectional"))
    )
    (net (code "40") (name "unconnected-(U2-P2.6{slash}PM_ACLK-Pad24)") (class "Default")
      (node (ref "U2") (pin "24") (pinfunction "P2.6/PM_ACLK_24") (pintype "bidirectional"))
    )
    (net (code "41") (name "unconnected-(U2-PJ.0{slash}TDO-Pad35)") (class "Default")
      (node (ref "U2") (pin "35") (pinfunction "PJ.0/TDO_35") (pintype "bidirectional"))
    )
    (net (code "42") (name "unconnected-(U2-PJ.1{slash}TDI{slash}TCLK-Pad36)") (class "Default")
      (node (ref "U2") (pin "36") (pinfunction "PJ.1/TDI/TCLK_36") (pintype "bidirectional"))
    )
    (net (code "43") (name "unconnected-(U2-PJ.2{slash}TMS-Pad37)") (class "Default")
      (node (ref "U2") (pin "37") (pinfunction "PJ.2/TMS_37") (pintype "bidirectional"))
    )
    (net (code "44") (name "unconnected-(U2-PJ.3{slash}TCK-Pad38)") (class "Default")
      (node (ref "U2") (pin "38") (pinfunction "PJ.3/TCK_38") (pintype "bidirectional"))
    )
  )
)
